# peripheral.net
KiCad netlist of a schematic drawn in Altium Designer
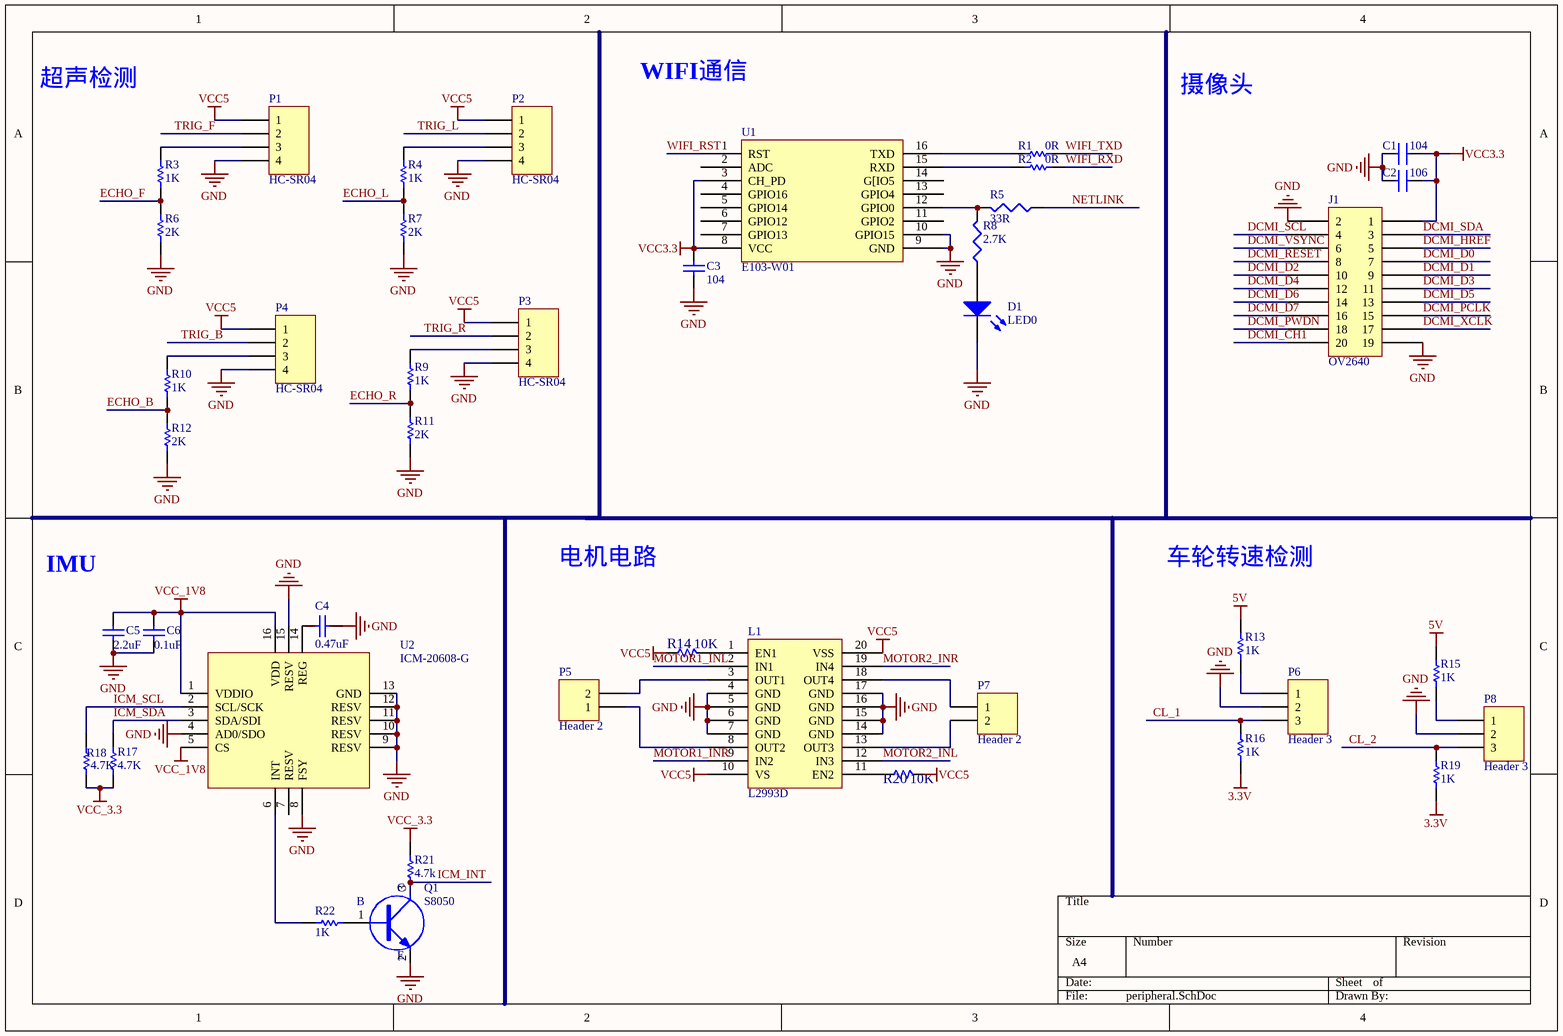
[diagram p0: peripheral.SchDoc]

(export (version "E")
  (design (tool "Eeschema 10.0.6"))
  (components
    (comp (ref "C1")
      (value "104")
      (footprint "C0603")
      (description "Capacitor")
      (libsource (lib "wifi_car") (part "CAP_9"))
    )
    (comp (ref "C2")
      (value "106")
      (footprint "C0603")
      (description "Capacitor")
      (libsource (lib "wifi_car") (part "CAP_9"))
    )
    (comp (ref "C3")
      (value "104")
      (footprint "0603C")
      (description "Capacitor")
      (fields (field (name "PUBLISHER") "Altium Limited"))
      (libsource (lib "wifi_car") (part "Cap_1"))
    )
    (comp (ref "C4")
      (value "0.47uF")
      (footprint "0603C")
      (description "Capacitor")
      (fields (field (name "PUBLISHER") "Altium Limited"))
      (libsource (lib "wifi_car") (part "Cap_1"))
    )
    (comp (ref "C5")
      (value "2.2uF")
      (footprint "0603C")
      (description "Capacitor")
      (fields (field (name "PUBLISHER") "Altium Limited"))
      (libsource (lib "wifi_car") (part "Cap_1"))
    )
    (comp (ref "C6")
      (value "0.1uF")
      (footprint "0603C")
      (description "Capacitor")
      (fields (field (name "PUBLISHER") "Altium Limited"))
      (libsource (lib "wifi_car") (part "Cap_1"))
    )
    (comp (ref "D1")
      (value "LED0")
      (footprint "0603LED")
      (description "Typical INFRARED GaAs LED")
      (fields (field (name "PUBLISHER") "Altium Limited"))
      (libsource (lib "Miscellaneous Devices") (part "LED0"))
    )
    (comp (ref "J1") (value "OV2640") (libsource (lib "wifi_car") (part "OV2640")))
    (comp (ref "L1") (value "L2993D") (libsource (lib "wifi_car") (part "L2993D")))
    (comp (ref "P1")
      (value "HC-SR04")
      (footprint "HDR1X4")
      (description "Header, 4-Pin")
      (fields (field (name "PUBLISHER") "Altium Limited"))
      (libsource (lib "Miscellaneous Connectors") (part "Header 4"))
    )
    (comp (ref "P2")
      (value "HC-SR04")
      (footprint "HDR1X4")
      (description "Header, 4-Pin")
      (fields (field (name "PUBLISHER") "Altium Limited"))
      (libsource (lib "Miscellaneous Connectors") (part "Header 4"))
    )
    (comp (ref "P3")
      (value "HC-SR04")
      (footprint "HDR1X4")
      (description "Header, 4-Pin")
      (fields (field (name "PUBLISHER") "Altium Limited"))
      (libsource (lib "Miscellaneous Connectors") (part "Header 4"))
    )
    (comp (ref "P4")
      (value "HC-SR04")
      (footprint "HDR1X4")
      (description "Header, 4-Pin")
      (fields (field (name "PUBLISHER") "Altium Limited"))
      (libsource (lib "Miscellaneous Connectors") (part "Header 4"))
    )
    (comp (ref "P5")
      (value "Header 2")
      (footprint "HDR1X2")
      (description "Header, 2-Pin")
      (fields (field (name "PUBLISHER") "Altium Limited"))
      (libsource (lib "wifi_car") (part "Header 2_2"))
    )
    (comp (ref "P6")
      (value "Header 3")
      (footprint "CON3")
      (description "Header, 3-Pin")
      (fields (field (name "PUBLISHER") "Altium Limited"))
      (libsource (lib "Miscellaneous Connectors") (part "Header 3"))
    )
    (comp (ref "P7")
      (value "Header 2")
      (footprint "HDR1X2")
      (description "Header, 2-Pin")
      (fields (field (name "PUBLISHER") "Altium Limited"))
      (libsource (lib "") (part "Header 2_2_1"))
    )
    (comp (ref "P8")
      (value "Header 3")
      (footprint "CON3")
      (description "Header, 3-Pin")
      (fields (field (name "PUBLISHER") "Altium Limited"))
      (libsource (lib "Miscellaneous Connectors") (part "Header 3"))
    )
    (comp (ref "Q1") (value "S8050") (footprint "SOT-23") (libsource (lib "*") (part "NPN_1")))
    (comp (ref "R1")
      (value "0R")
      (footprint "0603R")
      (description "Resistor")
      (fields (field (name "PUBLISHER") "Altium Limited"))
      (libsource (lib "wifi_car") (part "Res1_4"))
    )
    (comp (ref "R2")
      (value "0R")
      (footprint "0603R")
      (description "Resistor")
      (fields (field (name "PUBLISHER") "Altium Limited"))
      (libsource (lib "wifi_car") (part "Res1_4"))
    )
    (comp (ref "R3")
      (value "1K")
      (footprint "0603C")
      (description "Resistor")
      (fields (field (name "PUBLISHER") "Altium Limited"))
      (libsource (lib "Miscellaneous Devices") (part "Res1"))
    )
    (comp (ref "R4")
      (value "1K")
      (footprint "0603C")
      (description "Resistor")
      (fields (field (name "PUBLISHER") "Altium Limited"))
      (libsource (lib "Miscellaneous Devices") (part "Res1"))
    )
    (comp (ref "R5") (value "33R") (footprint "0603R") (libsource (lib "*") (part "RES1")))
    (comp (ref "R6")
      (value "2K")
      (footprint "0603C")
      (description "Resistor")
      (fields (field (name "PUBLISHER") "Altium Limited"))
      (libsource (lib "Miscellaneous Devices") (part "Res1"))
    )
    (comp (ref "R7")
      (value "2K")
      (footprint "0603C")
      (description "Resistor")
      (fields (field (name "PUBLISHER") "Altium Limited"))
      (libsource (lib "Miscellaneous Devices") (part "Res1"))
    )
    (comp (ref "R8") (value "2.7K") (footprint "0603R") (libsource (lib "*") (part "RES1")))
    (comp (ref "R9")
      (value "1K")
      (footprint "0603C")
      (description "Resistor")
      (fields (field (name "PUBLISHER") "Altium Limited"))
      (libsource (lib "Miscellaneous Devices") (part "Res1"))
    )
    (comp (ref "R10")
      (value "1K")
      (footprint "0603C")
      (description "Resistor")
      (fields (field (name "PUBLISHER") "Altium Limited"))
      (libsource (lib "Miscellaneous Devices") (part "Res1"))
    )
    (comp (ref "R11")
      (value "2K")
      (footprint "0603C")
      (description "Resistor")
      (fields (field (name "PUBLISHER") "Altium Limited"))
      (libsource (lib "Miscellaneous Devices") (part "Res1"))
    )
    (comp (ref "R12")
      (value "2K")
      (footprint "0603C")
      (description "Resistor")
      (fields (field (name "PUBLISHER") "Altium Limited"))
      (libsource (lib "Miscellaneous Devices") (part "Res1"))
    )
    (comp (ref "R13")
      (value "1K")
      (footprint "0603C")
      (description "Resistor")
      (fields (field (name "PUBLISHER") "Altium Limited"))
      (libsource (lib "Miscellaneous Devices") (part "Res1"))
    )
    (comp (ref "R14")
      (value "10K")
      (footprint "R0603")
      (description "Resistor")
      (libsource (lib "wifi_car") (part "R_1"))
    )
    (comp (ref "R15")
      (value "1K")
      (footprint "0603C")
      (description "Resistor")
      (fields (field (name "PUBLISHER") "Altium Limited"))
      (libsource (lib "Miscellaneous Devices") (part "Res1"))
    )
    (comp (ref "R16")
      (value "1K")
      (footprint "0603C")
      (description "Resistor")
      (fields (field (name "PUBLISHER") "Altium Limited"))
      (libsource (lib "Miscellaneous Devices") (part "Res1"))
    )
    (comp (ref "R17")
      (value "4.7K")
      (footprint "0603C")
      (description "Resistor")
      (fields (field (name "PUBLISHER") "Altium Limited"))
      (libsource (lib "Miscellaneous Devices") (part "Res1"))
    )
    (comp (ref "R18")
      (value "4.7K")
      (footprint "0603C")
      (description "Resistor")
      (fields (field (name "PUBLISHER") "Altium Limited"))
      (libsource (lib "Miscellaneous Devices") (part "Res1"))
    )
    (comp (ref "R19")
      (value "1K")
      (footprint "0603C")
      (description "Resistor")
      (fields (field (name "PUBLISHER") "Altium Limited"))
      (libsource (lib "Miscellaneous Devices") (part "Res1"))
    )
    (comp (ref "R20")
      (value "10K")
      (footprint "R0603")
      (description "Resistor")
      (libsource (lib "wifi_car") (part "R_1"))
    )
    (comp (ref "R21")
      (value "4.7k")
      (footprint "0603C")
      (description "Resistor")
      (fields (field (name "PUBLISHER") "Altium Limited"))
      (libsource (lib "Miscellaneous Devices") (part "Res1"))
    )
    (comp (ref "R22")
      (value "1K")
      (footprint "0603C")
      (description "Resistor")
      (fields (field (name "PUBLISHER") "Altium Limited"))
      (libsource (lib "Miscellaneous Devices") (part "Res1"))
    )
    (comp (ref "U1")
      (value "E103-W01")
      (footprint "E103-W01")
      (description "Diode")
      (libsource (lib "DCQ-01") (part "E103-W01"))
    )
    (comp (ref "U2")
      (value "ICM-20608-G")
      (footprint "IC268G")
      (description "Capacitor")
      (libsource (lib "ZNXC_V1.0") (part "DS-000081"))
    )
  )
  (nets
    (net (code "1") (name "/CL_1") (class "Default")
      (node (ref "P6") (pin "3") (pinfunction "3_3") (pintype "passive"))
      (node (ref "R16") (pin "2") (pinfunction "2_2") (pintype "passive"))
    )
    (net (code "2") (name "/CL_2") (class "Default")
      (node (ref "P8") (pin "3") (pinfunction "3_3") (pintype "passive"))
      (node (ref "R19") (pin "2") (pinfunction "2_2") (pintype "passive"))
    )
    (net (code "3") (name "/DCMI_CH1") (class "Default")
      (node (ref "J1") (pin "20") (pinfunction "20_20") (pintype "passive"))
    )
    (net (code "4") (name "/DCMI_D0") (class "Default")
      (node (ref "J1") (pin "7") (pinfunction "7_7") (pintype "passive"))
    )
    (net (code "5") (name "/DCMI_D1") (class "Default")
      (node (ref "J1") (pin "9") (pinfunction "9_9") (pintype "passive"))
    )
    (net (code "6") (name "/DCMI_D2") (class "Default")
      (node (ref "J1") (pin "10") (pinfunction "10_10") (pintype "passive"))
    )
    (net (code "7") (name "/DCMI_D3") (class "Default")
      (node (ref "J1") (pin "11") (pinfunction "11_11") (pintype "passive"))
    )
    (net (code "8") (name "/DCMI_D4") (class "Default")
      (node (ref "J1") (pin "12") (pinfunction "12_12") (pintype "passive"))
    )
    (net (code "9") (name "/DCMI_D5") (class "Default")
      (node (ref "J1") (pin "13") (pinfunction "13_13") (pintype "passive"))
    )
    (net (code "10") (name "/DCMI_D6") (class "Default")
      (node (ref "J1") (pin "14") (pinfunction "14_14") (pintype "passive"))
    )
    (net (code "11") (name "/DCMI_D7") (class "Default")
      (node (ref "J1") (pin "16") (pinfunction "16_16") (pintype "passive"))
    )
    (net (code "12") (name "/DCMI_HREF") (class "Default")
      (node (ref "J1") (pin "5") (pinfunction "5_5") (pintype "passive"))
    )
    (net (code "13") (name "/DCMI_PCLK") (class "Default")
      (node (ref "J1") (pin "15") (pinfunction "15_15") (pintype "passive"))
    )
    (net (code "14") (name "/DCMI_PWDN") (class "Default")
      (node (ref "J1") (pin "18") (pinfunction "18_18") (pintype "passive"))
    )
    (net (code "15") (name "/DCMI_RESET") (class "Default")
      (node (ref "J1") (pin "8") (pinfunction "8_8") (pintype "passive"))
    )
    (net (code "16") (name "/DCMI_SCL") (class "Default")
      (node (ref "J1") (pin "4") (pinfunction "4_4") (pintype "passive"))
    )
    (net (code "17") (name "/DCMI_SDA") (class "Default")
      (node (ref "J1") (pin "3") (pinfunction "3_3") (pintype "passive"))
    )
    (net (code "18") (name "/DCMI_VSYNC") (class "Default")
      (node (ref "J1") (pin "6") (pinfunction "6_6") (pintype "passive"))
    )
    (net (code "19") (name "/DCMI_XCLK") (class "Default")
      (node (ref "J1") (pin "17") (pinfunction "17_17") (pintype "passive"))
    )
    (net (code "20") (name "/ECHO_B") (class "Default")
      (node (ref "R10") (pin "1") (pinfunction "1_1") (pintype "passive"))
      (node (ref "R12") (pin "2") (pinfunction "2_2") (pintype "passive"))
    )
    (net (code "21") (name "/ECHO_F") (class "Default")
      (node (ref "R3") (pin "1") (pinfunction "1_1") (pintype "passive"))
      (node (ref "R6") (pin "2") (pinfunction "2_2") (pintype "passive"))
    )
    (net (code "22") (name "/ECHO_L") (class "Default")
      (node (ref "R4") (pin "1") (pinfunction "1_1") (pintype "passive"))
      (node (ref "R7") (pin "2") (pinfunction "2_2") (pintype "passive"))
    )
    (net (code "23") (name "/ECHO_R") (class "Default")
      (node (ref "R11") (pin "2") (pinfunction "2_2") (pintype "passive"))
      (node (ref "R9") (pin "1") (pinfunction "1_1") (pintype "passive"))
    )
    (net (code "24") (name "/ICM_INT") (class "Default")
      (node (ref "Q1") (pin "3") (pinfunction "C_3") (pintype "passive"))
      (node (ref "R21") (pin "1") (pinfunction "1_1") (pintype "passive"))
    )
    (net (code "25") (name "/ICM_SCL") (class "Default")
      (node (ref "R18") (pin "2") (pinfunction "2_2") (pintype "passive"))
      (node (ref "U2") (pin "2") (pinfunction "SCL/SCK_2") (pintype "passive"))
    )
    (net (code "26") (name "/ICM_SDA") (class "Default")
      (node (ref "R17") (pin "1") (pinfunction "1_1") (pintype "passive"))
      (node (ref "U2") (pin "3") (pinfunction "SDA/SDI_3") (pintype "passive"))
    )
    (net (code "27") (name "/MOTOR1_INL") (class "Default")
      (node (ref "L1") (pin "2") (pinfunction "IN1_2") (pintype "passive"))
    )
    (net (code "28") (name "/MOTOR1_INR") (class "Default")
      (node (ref "L1") (pin "9") (pinfunction "IN2_9") (pintype "passive"))
    )
    (net (code "29") (name "/MOTOR2_INL") (class "Default")
      (node (ref "L1") (pin "12") (pinfunction "IN3_12") (pintype "passive"))
    )
    (net (code "30") (name "/MOTOR2_INR") (class "Default")
      (node (ref "L1") (pin "19") (pinfunction "IN4_19") (pintype "passive"))
    )
    (net (code "31") (name "/NETLINK") (class "Default") (node (ref "R5") (pin "1") (pintype "passive")))
    (net (code "32") (name "/TRIG_B") (class "Default")
      (node (ref "P4") (pin "2") (pinfunction "2_2") (pintype "passive"))
    )
    (net (code "33") (name "/TRIG_F") (class "Default")
      (node (ref "P1") (pin "2") (pinfunction "2_2") (pintype "passive"))
    )
    (net (code "34") (name "/TRIG_L") (class "Default")
      (node (ref "P2") (pin "2") (pinfunction "2_2") (pintype "passive"))
    )
    (net (code "35") (name "/TRIG_R") (class "Default")
      (node (ref "P3") (pin "2") (pinfunction "2_2") (pintype "passive"))
    )
    (net (code "36") (name "/WIFI_RST") (class "Default")
      (node (ref "U1") (pin "1") (pinfunction "RST_1") (pintype "passive"))
    )
    (net (code "37") (name "/WIFI_RXD") (class "Default")
      (node (ref "R2") (pin "2") (pinfunction "2_2") (pintype "passive"))
    )
    (net (code "38") (name "/WIFI_TXD") (class "Default")
      (node (ref "R1") (pin "2") (pinfunction "2_2") (pintype "passive"))
    )
    (net (code "39") (name "3.3V") (class "Default")
      (node (ref "R16") (pin "1") (pinfunction "1_1") (pintype "passive"))
      (node (ref "R19") (pin "1") (pinfunction "1_1") (pintype "passive"))
    )
    (net (code "40") (name "5V") (class "Default")
      (node (ref "R13") (pin "2") (pinfunction "2_2") (pintype "passive"))
      (node (ref "R15") (pin "2") (pinfunction "2_2") (pintype "passive"))
    )
    (net (code "41") (name "GND") (class "Default")
      (node (ref "C1") (pin "1") (pinfunction "1_1") (pintype "passive"))
      (node (ref "C2") (pin "1") (pinfunction "1_1") (pintype "passive"))
      (node (ref "C3") (pin "1") (pinfunction "1_1") (pintype "passive"))
      (node (ref "C4") (pin "2") (pinfunction "2_2") (pintype "passive"))
      (node (ref "C5") (pin "1") (pinfunction "1_1") (pintype "passive"))
      (node (ref "C6") (pin "1") (pinfunction "1_1") (pintype "passive"))
      (node (ref "D1") (pin "2") (pinfunction "K_2") (pintype "passive"))
      (node (ref "J1") (pin "19") (pinfunction "19_19") (pintype "passive"))
      (node (ref "J1") (pin "2") (pinfunction "2_2") (pintype "passive"))
      (node (ref "L1") (pin "14") (pinfunction "GND_14") (pintype "passive"))
      (node (ref "L1") (pin "15") (pinfunction "GND_15") (pintype "passive"))
      (node (ref "L1") (pin "16") (pinfunction "GND_16") (pintype "passive"))
      (node (ref "L1") (pin "17") (pinfunction "GND_17") (pintype "passive"))
      (node (ref "L1") (pin "4") (pinfunction "GND_4") (pintype "passive"))
      (node (ref "L1") (pin "5") (pinfunction "GND_5") (pintype "passive"))
      (node (ref "L1") (pin "6") (pinfunction "GND_6") (pintype "passive"))
      (node (ref "L1") (pin "7") (pinfunction "GND_7") (pintype "passive"))
      (node (ref "P1") (pin "4") (pinfunction "4_4") (pintype "passive"))
      (node (ref "P2") (pin "4") (pinfunction "4_4") (pintype "passive"))
      (node (ref "P3") (pin "4") (pinfunction "4_4") (pintype "passive"))
      (node (ref "P4") (pin "4") (pinfunction "4_4") (pintype "passive"))
      (node (ref "P6") (pin "2") (pinfunction "2_2") (pintype "passive"))
      (node (ref "P8") (pin "2") (pinfunction "2_2") (pintype "passive"))
      (node (ref "Q1") (pin "2") (pinfunction "E_2") (pintype "passive"))
      (node (ref "R11") (pin "1") (pinfunction "1_1") (pintype "passive"))
      (node (ref "R12") (pin "1") (pinfunction "1_1") (pintype "passive"))
      (node (ref "R6") (pin "1") (pinfunction "1_1") (pintype "passive"))
      (node (ref "R7") (pin "1") (pinfunction "1_1") (pintype "passive"))
      (node (ref "U1") (pin "10") (pinfunction "GPIO15_10") (pintype "passive"))
      (node (ref "U1") (pin "9") (pinfunction "GND_9") (pintype "passive"))
      (node (ref "U2") (pin "10") (pinfunction "RESV_10") (pintype "passive"))
      (node (ref "U2") (pin "11") (pinfunction "RESV_11") (pintype "passive"))
      (node (ref "U2") (pin "12") (pinfunction "RESV_12") (pintype "passive"))
      (node (ref "U2") (pin "13") (pinfunction "GND_13") (pintype "passive"))
      (node (ref "U2") (pin "15") (pinfunction "RESV_15") (pintype "passive"))
      (node (ref "U2") (pin "4") (pinfunction "AD0/SDO_4") (pintype "passive"))
      (node (ref "U2") (pin "8") (pinfunction "FSY_8") (pintype "passive"))
      (node (ref "U2") (pin "9") (pinfunction "RESV_9") (pintype "passive"))
    )
    (net (code "42") (name "Net-(D1-A)") (class "Default")
      (node (ref "D1") (pin "1") (pinfunction "A_1") (pintype "passive"))
      (node (ref "R8") (pin "1") (pintype "passive"))
    )
    (net (code "43") (name "Net-(L1-EN1)") (class "Default")
      (node (ref "L1") (pin "1") (pinfunction "EN1_1") (pintype "passive"))
      (node (ref "R14") (pin "2") (pinfunction "2_2") (pintype "passive"))
    )
    (net (code "44") (name "Net-(L1-EN2)") (class "Default")
      (node (ref "L1") (pin "11") (pinfunction "EN2_11") (pintype "passive"))
      (node (ref "R20") (pin "1") (pinfunction "1_1") (pintype "passive"))
    )
    (net (code "45") (name "Net-(L1-OUT1)") (class "Default")
      (node (ref "L1") (pin "3") (pinfunction "OUT1_3") (pintype "passive"))
      (node (ref "P5") (pin "2") (pinfunction "2_2") (pintype "passive"))
    )
    (net (code "46") (name "Net-(L1-OUT2)") (class "Default")
      (node (ref "L1") (pin "8") (pinfunction "OUT2_8") (pintype "passive"))
      (node (ref "P5") (pin "1") (pinfunction "1_1") (pintype "passive"))
    )
    (net (code "47") (name "Net-(L1-OUT3)") (class "Default")
      (node (ref "L1") (pin "13") (pinfunction "OUT3_13") (pintype "passive"))
      (node (ref "P7") (pin "2") (pinfunction "2_2") (pintype "passive"))
    )
    (net (code "48") (name "Net-(L1-OUT4)") (class "Default")
      (node (ref "L1") (pin "18") (pinfunction "OUT4_18") (pintype "passive"))
      (node (ref "P7") (pin "1") (pinfunction "1_1") (pintype "passive"))
    )
    (net (code "49") (name "Net-(P1-Pad3)") (class "Default")
      (node (ref "P1") (pin "3") (pinfunction "3_3") (pintype "passive"))
      (node (ref "R3") (pin "2") (pinfunction "2_2") (pintype "passive"))
    )
    (net (code "50") (name "Net-(P2-Pad3)") (class "Default")
      (node (ref "P2") (pin "3") (pinfunction "3_3") (pintype "passive"))
      (node (ref "R4") (pin "2") (pinfunction "2_2") (pintype "passive"))
    )
    (net (code "51") (name "Net-(P3-Pad3)") (class "Default")
      (node (ref "P3") (pin "3") (pinfunction "3_3") (pintype "passive"))
      (node (ref "R9") (pin "2") (pinfunction "2_2") (pintype "passive"))
    )
    (net (code "52") (name "Net-(P4-Pad3)") (class "Default")
      (node (ref "P4") (pin "3") (pinfunction "3_3") (pintype "passive"))
      (node (ref "R10") (pin "2") (pinfunction "2_2") (pintype "passive"))
    )
    (net (code "53") (name "Net-(P6-Pad1)") (class "Default")
      (node (ref "P6") (pin "1") (pinfunction "1_1") (pintype "passive"))
      (node (ref "R13") (pin "1") (pinfunction "1_1") (pintype "passive"))
    )
    (net (code "54") (name "Net-(P8-Pad1)") (class "Default")
      (node (ref "P8") (pin "1") (pinfunction "1_1") (pintype "passive"))
      (node (ref "R15") (pin "1") (pinfunction "1_1") (pintype "passive"))
    )
    (net (code "55") (name "Net-(Q1-B)") (class "Default")
      (node (ref "Q1") (pin "1") (pinfunction "B_1") (pintype "passive"))
      (node (ref "R22") (pin "1") (pinfunction "1_1") (pintype "passive"))
    )
    (net (code "56") (name "Net-(U1-GPIO0)") (class "Default")
      (node (ref "R5") (pin "2") (pintype "passive"))
      (node (ref "R8") (pin "2") (pintype "passive"))
      (node (ref "U1") (pin "12") (pinfunction "GPIO0_12") (pintype "passive"))
    )
    (net (code "57") (name "Net-(U1-RXD)") (class "Default")
      (node (ref "R2") (pin "1") (pinfunction "1_1") (pintype "passive"))
      (node (ref "U1") (pin "15") (pinfunction "RXD_15") (pintype "passive"))
    )
    (net (code "58") (name "Net-(U1-TXD)") (class "Default")
      (node (ref "R1") (pin "1") (pinfunction "1_1") (pintype "passive"))
      (node (ref "U1") (pin "16") (pinfunction "TXD_16") (pintype "passive"))
    )
    (net (code "59") (name "Net-(U2-INT)") (class "Default")
      (node (ref "R22") (pin "2") (pinfunction "2_2") (pintype "passive"))
      (node (ref "U2") (pin "6") (pinfunction "INT_6") (pintype "passive"))
    )
    (net (code "60") (name "Net-(U2-REG)") (class "Default")
      (node (ref "C4") (pin "1") (pinfunction "1_1") (pintype "passive"))
      (node (ref "U2") (pin "14") (pinfunction "REG_14") (pintype "passive"))
    )
    (net (code "61") (name "VCC3.3") (class "Default")
      (node (ref "C1") (pin "2") (pinfunction "2_2") (pintype "passive"))
      (node (ref "C2") (pin "2") (pinfunction "2_2") (pintype "passive"))
      (node (ref "C3") (pin "2") (pinfunction "2_2") (pintype "passive"))
      (node (ref "J1") (pin "1") (pinfunction "1_1") (pintype "passive"))
      (node (ref "U1") (pin "3") (pinfunction "CH_PD_3") (pintype "passive"))
      (node (ref "U1") (pin "8") (pinfunction "VCC_8") (pintype "passive"))
    )
    (net (code "62") (name "VCC5") (class "Default")
      (node (ref "L1") (pin "10") (pinfunction "VS_10") (pintype "passive"))
      (node (ref "L1") (pin "20") (pinfunction "VSS_20") (pintype "passive"))
      (node (ref "P1") (pin "1") (pinfunction "1_1") (pintype "passive"))
      (node (ref "P2") (pin "1") (pinfunction "1_1") (pintype "passive"))
      (node (ref "P3") (pin "1") (pinfunction "1_1") (pintype "passive"))
      (node (ref "P4") (pin "1") (pinfunction "1_1") (pintype "passive"))
      (node (ref "R14") (pin "1") (pinfunction "1_1") (pintype "passive"))
      (node (ref "R20") (pin "2") (pinfunction "2_2") (pintype "passive"))
    )
    (net (code "63") (name "VCC_1V8") (class "Default")
      (node (ref "C5") (pin "2") (pinfunction "2_2") (pintype "passive"))
      (node (ref "C6") (pin "2") (pinfunction "2_2") (pintype "passive"))
      (node (ref "U2") (pin "1") (pinfunction "VDDIO_1") (pintype "passive"))
      (node (ref "U2") (pin "16") (pinfunction "VDD_16") (pintype "passive"))
      (node (ref "U2") (pin "5") (pinfunction "CS_5") (pintype "passive"))
    )
    (net (code "64") (name "VCC_3.3") (class "Default")
      (node (ref "R17") (pin "2") (pinfunction "2_2") (pintype "passive"))
      (node (ref "R18") (pin "1") (pinfunction "1_1") (pintype "passive"))
      (node (ref "R21") (pin "2") (pinfunction "2_2") (pintype "passive"))
    )
    (net (code "65") (name "unconnected-(U1-ADC-Pad2)") (class "Default")
      (node (ref "U1") (pin "2") (pinfunction "ADC_2") (pintype "passive"))
    )
    (net (code "66") (name "unconnected-(U1-GPIO2-Pad11)") (class "Default")
      (node (ref "U1") (pin "11") (pinfunction "GPIO2_11") (pintype "passive"))
    )
    (net (code "67") (name "unconnected-(U1-GPIO4-Pad13)") (class "Default")
      (node (ref "U1") (pin "13") (pinfunction "GPIO4_13") (pintype "passive"))
    )
    (net (code "68") (name "unconnected-(U1-GPIO12-Pad6)") (class "Default")
      (node (ref "U1") (pin "6") (pinfunction "GPIO12_6") (pintype "passive"))
    )
    (net (code "69") (name "unconnected-(U1-GPIO13-Pad7)") (class "Default")
      (node (ref "U1") (pin "7") (pinfunction "GPIO13_7") (pintype "passive"))
    )
    (net (code "70") (name "unconnected-(U1-GPIO14-Pad5)") (class "Default")
      (node (ref "U1") (pin "5") (pinfunction "GPIO14_5") (pintype "passive"))
    )
    (net (code "71") (name "unconnected-(U1-GPIO16-Pad4)") (class "Default")
      (node (ref "U1") (pin "4") (pinfunction "GPIO16_4") (pintype "passive"))
    )
    (net (code "72") (name "unconnected-(U1-G[IO5-Pad14)") (class "Default")
      (node (ref "U1") (pin "14") (pinfunction "G[IO5_14") (pintype "passive"))
    )
    (net (code "73") (name "unconnected-(U2-RESV-Pad7)") (class "Default")
      (node (ref "U2") (pin "7") (pinfunction "RESV_7") (pintype "passive"))
    )
  )
)
